# Sheet1.net
KiCad netlist of a schematic drawn in Altium Designer
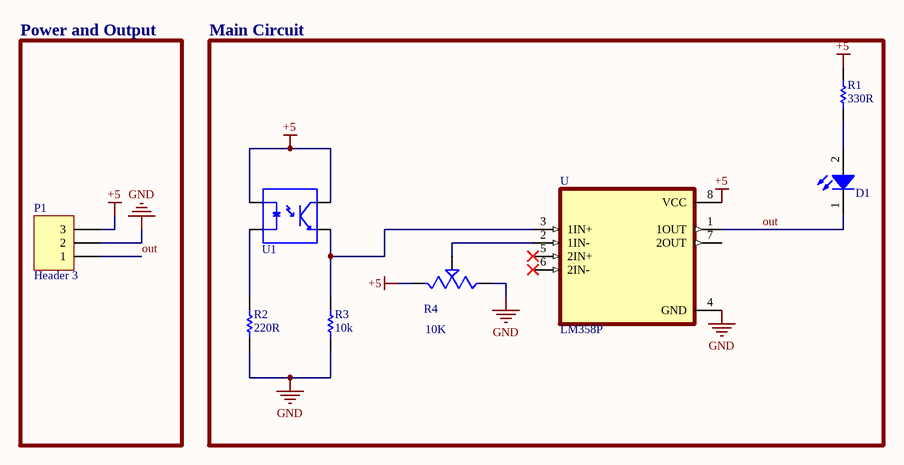
[diagram p0: Sheet1.SchDoc]

(export (version "E")
  (design (tool "Eeschema 10.0.6"))
  (components
    (comp (ref "D1")
      (value "15400385A3590")
      (footprint "WL-TIRW_D3.9H5.3")
      (description "WL-TIRW THT Infrared Round Waterclear, D3.9H5.3, 60mW/sr, 1.5V, 35deg")
      (fields (field (name "MANUFACTURER") "Wurth Elektronik"))
      (libsource (lib "WL-TIRW") (part "15400385A3590"))
    )
    (comp (ref "P1")
      (value "Header 3")
      (footprint "HDR1X3")
      (description "Header, 3-Pin")
      (fields (field (name "PUBLISHER") "Altium Limited"))
      (libsource (lib "Miscellaneous Connectors") (part "Header 3"))
    )
    (comp (ref "R1")
      (value "330R")
      (footprint "AXIAL-0.3")
      (description "Resistor")
      (fields (field (name "PUBLISHER") "Altium Limited"))
      (libsource (lib "Miscellaneous Devices") (part "Res1"))
    )
    (comp (ref "R2")
      (value "220R")
      (footprint "AXIAL-0.3")
      (description "Resistor")
      (fields (field (name "PUBLISHER") "Altium Limited"))
      (libsource (lib "Miscellaneous Devices") (part "Res1"))
    )
    (comp (ref "R3")
      (value "10k")
      (footprint "AXIAL-0.3")
      (description "Resistor")
      (fields (field (name "PUBLISHER") "Altium Limited"))
      (libsource (lib "Miscellaneous Devices") (part "Res1"))
    )
    (comp (ref "R4")
      (value "10K")
      (footprint "TRIM_EVN-D8AA03B14")
      (description "10 kOhms 0.1W, 1/10W PC Pins Through Hole Trimmer Potentiometer Carbon 1 Turn Top Adjustment")
      (fields (field (name "MP") "EVN-D8AA03B14") (field (name "MF") "Panasonic Electronic"))
      (libsource (lib "SnapEDAsch") (part "EVN-D8AA03B14"))
    )
    (comp (ref "U")
      (value "LM358P")
      (footprint "DIP794W45P254L959H508Q8")
      (description "Dual Operational Amplifiers")
      (fields (field (name "MF") "Texas Instruments"))
      (libsource (lib "LM358P") (part "LM358P"))
    )
    (comp (ref "U1")
      (value "TCRT5000")
      (footprint "OPTO_TCRT5000")
      (description "Reflective Optical Sensor 0.591 _15mm_ PCB Mount")
      (fields (field (name "MF") "Vishay"))
      (libsource (lib "Schlib1") (part "TCRT5000"))
    )
  )
  (nets
    (net (code "1") (name "+5") (class "Default")
      (node (ref "P1") (pin "3") (pinfunction "3_3") (pintype "passive"))
      (node (ref "R1") (pin "2") (pinfunction "2_2") (pintype "passive"))
      (node (ref "R4") (pin "3") (pinfunction "3_3") (pintype "passive"))
      (node (ref "U") (pin "8") (pinfunction "VCC_8") (pintype "power_in"))
      (node (ref "U1") (pin "A") (pinfunction "A_A") (pintype "passive"))
      (node (ref "U1") (pin "COLL") (pinfunction "COLL_COLL") (pintype "passive"))
    )
    (net (code "2") (name "/out") (class "Default")
      (node (ref "D1") (pin "1") (pinfunction "K_1") (pintype "passive"))
      (node (ref "P1") (pin "1") (pinfunction "1_1") (pintype "passive"))
      (node (ref "U") (pin "1") (pinfunction "1OUT_1") (pintype "output"))
    )
    (net (code "3") (name "GND") (class "Default")
      (node (ref "P1") (pin "2") (pinfunction "2_2") (pintype "passive"))
      (node (ref "R2") (pin "1") (pinfunction "1_1") (pintype "passive"))
      (node (ref "R3") (pin "1") (pinfunction "1_1") (pintype "passive"))
      (node (ref "R4") (pin "1") (pinfunction "1_1") (pintype "passive"))
      (node (ref "U") (pin "4") (pinfunction "GND_4") (pintype "power_in"))
    )
    (net (code "4") (name "Net-(D1-A)") (class "Default")
      (node (ref "D1") (pin "2") (pinfunction "A_2") (pintype "passive"))
      (node (ref "R1") (pin "1") (pinfunction "1_1") (pintype "passive"))
    )
    (net (code "5") (name "Net-(R2-Pad2)") (class "Default")
      (node (ref "R2") (pin "2") (pinfunction "2_2") (pintype "passive"))
      (node (ref "U1") (pin "CATH") (pinfunction "CATH_CATH") (pintype "passive"))
    )
    (net (code "6") (name "Net-(U-1IN+)") (class "Default")
      (node (ref "R3") (pin "2") (pinfunction "2_2") (pintype "passive"))
      (node (ref "U") (pin "3") (pinfunction "1IN+_3") (pintype "input"))
      (node (ref "U1") (pin "E") (pinfunction "E_E") (pintype "passive"))
    )
    (net (code "7") (name "Net-(U-1IN-)") (class "Default")
      (node (ref "R4") (pin "2") (pinfunction "2_2") (pintype "passive"))
      (node (ref "U") (pin "2") (pinfunction "1IN-_2") (pintype "input"))
    )
    (net (code "8") (name "unconnected-(U-2IN+-Pad5)") (class "Default")
      (node (ref "U") (pin "5") (pinfunction "2IN+_5") (pintype "input+no_connect"))
    )
    (net (code "9") (name "unconnected-(U-2IN--Pad6)") (class "Default")
      (node (ref "U") (pin "6") (pinfunction "2IN-_6") (pintype "input+no_connect"))
    )
    (net (code "10") (name "unconnected-(U-2OUT-Pad7)") (class "Default")
      (node (ref "U") (pin "7") (pinfunction "2OUT_7") (pintype "output"))
    )
  )
)
